# arduino-shield.net
KiCad netlist of a schematic drawn in EAGLE
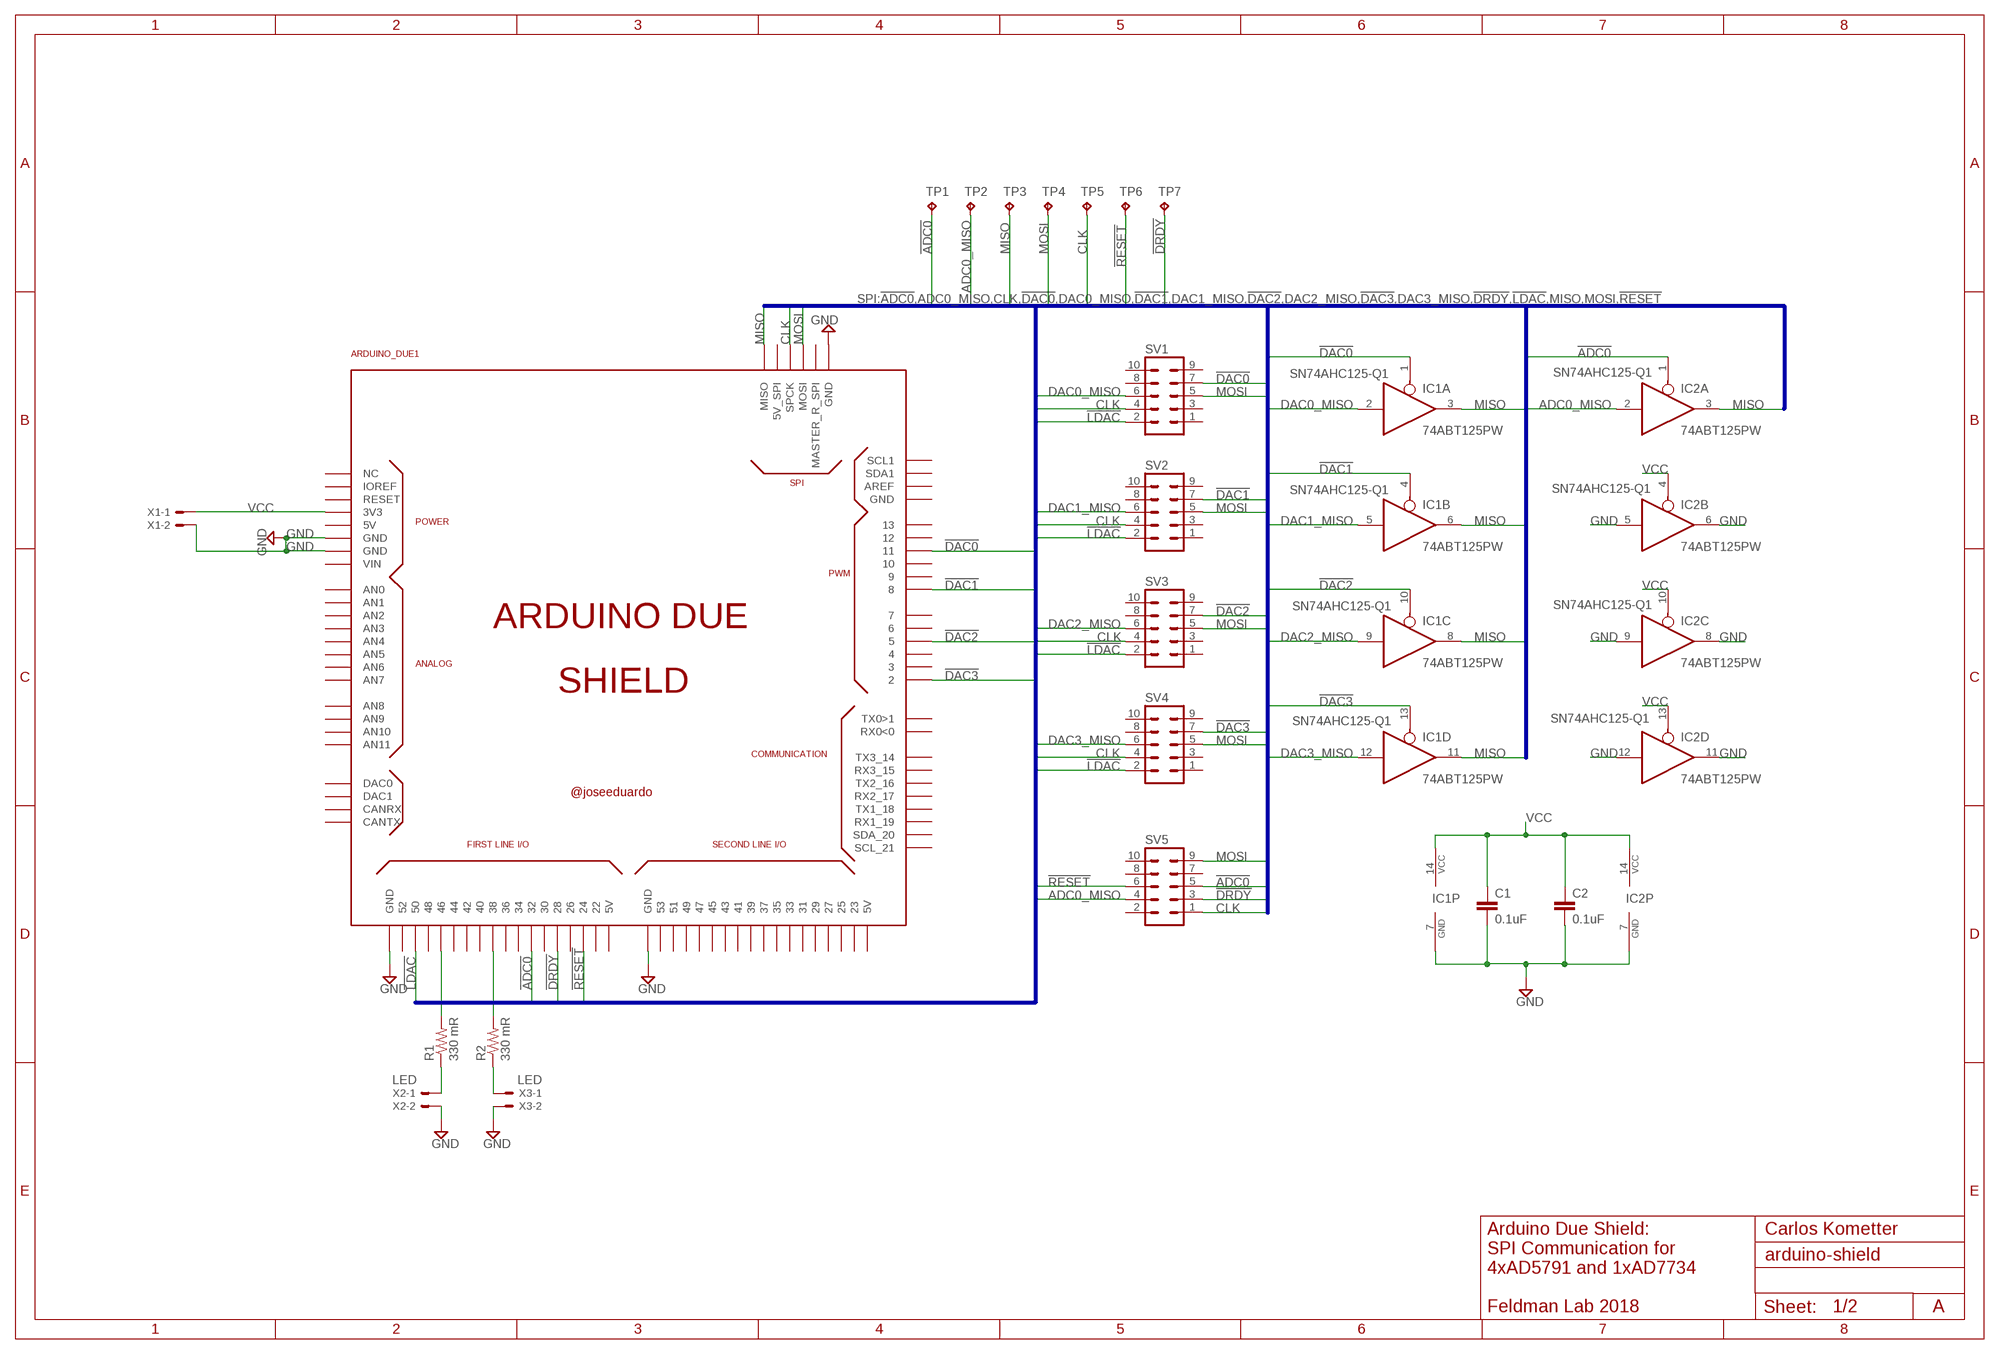
[diagram p0: schematic, sheet 1]
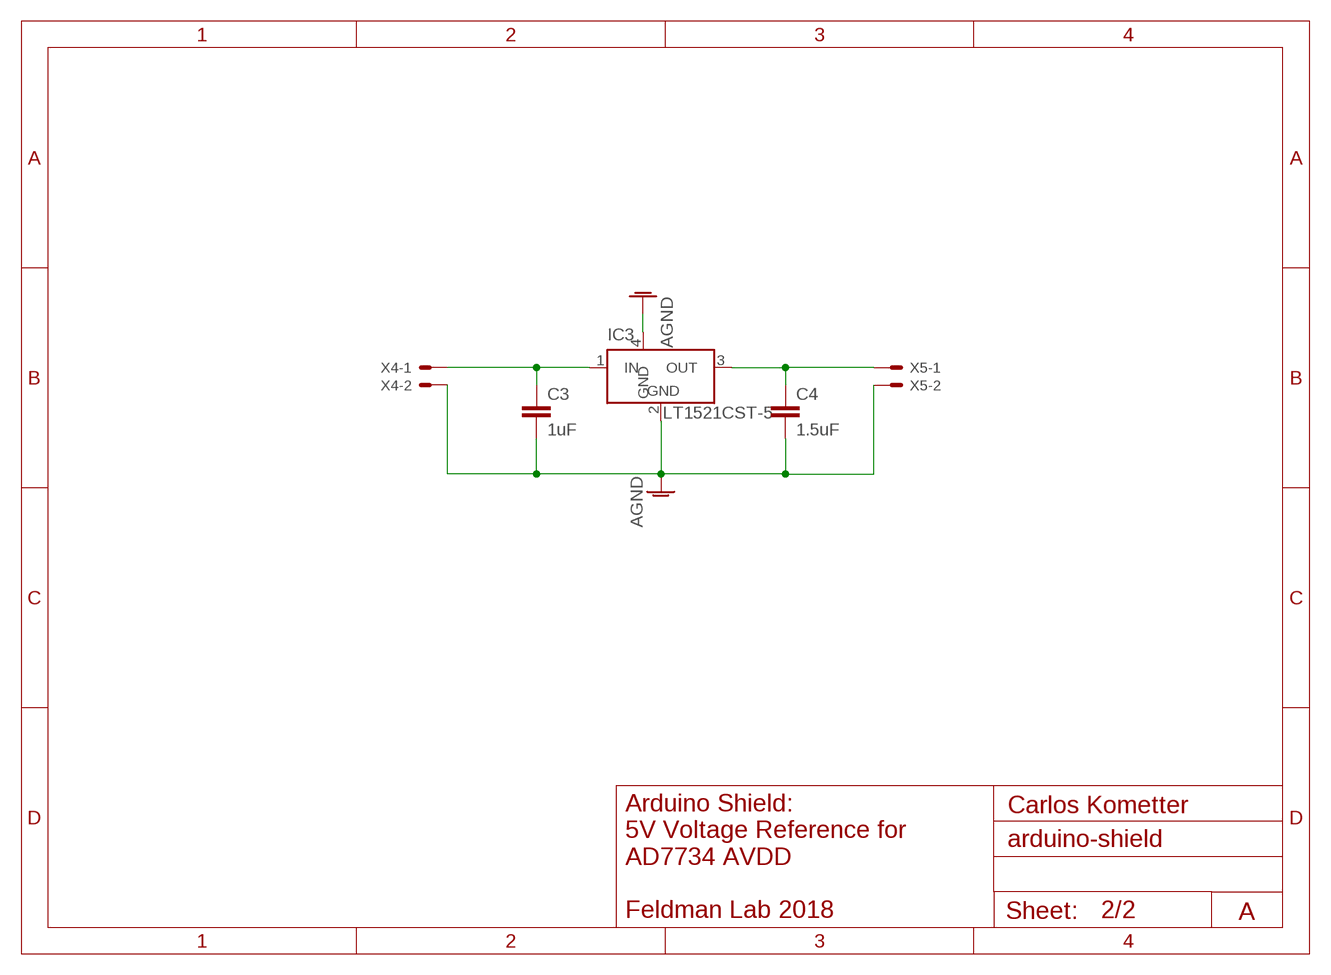
[diagram p1: schematic, sheet 2]

(export (version "E")
  (design (tool "Eeschema 10.0.6"))
  (components
    (comp (ref "C3")
      (value "1uF")
      (footprint "eagle-import:C0603")
      (libsource (lib "eagle-import") (part "C-EUC0603"))
    )
    (comp (ref "C4")
      (value "1.5uF")
      (footprint "eagle-import:C0603")
      (libsource (lib "eagle-import") (part "C-EUC0603"))
    )
    (comp (ref "IC3")
      (value "LT1129CST5")
      (footprint "eagle-import:SOT223")
      (fields (field (name "MPN") "LT1129CST-5#PBF"))
      (libsource (lib "eagle-import") (part "LT1129CST5"))
    )
    (comp (ref "X4")
      (value "22-23-2021")
      (footprint "eagle-import:22-23-2021")
      (fields (field (name "MF") "MOLEX"))
      (libsource (lib "eagle-import") (part "22-23-2021"))
    )
    (comp (ref "X5")
      (value "22-23-2021")
      (footprint "eagle-import:22-23-2021")
      (fields (field (name "MF") "MOLEX"))
      (libsource (lib "eagle-import") (part "22-23-2021"))
    )
    (comp (ref "ARDUINO_DUE1")
      (value "ARDUINO_DUE_SHIELD")
      (footprint "eagle-import:ARDUINO_DUE_SHIELD")
      (libsource (lib "eagle-import") (part "ARDUINO_DUE_SHIELD"))
    )
    (comp (ref "C1")
      (value "0.1uF")
      (footprint "eagle-import:C0603")
      (libsource (lib "eagle-import") (part "C-EUC0603"))
    )
    (comp (ref "C2")
      (value "0.1uF")
      (footprint "eagle-import:C0603")
      (libsource (lib "eagle-import") (part "C-EUC0603"))
    )
    (comp (ref "IC1")
      (value "74ABT125PW")
      (footprint "eagle-import:TSSOP14")
      (libsource (lib "eagle-import") (part "74125PWABT"))
    )
    (comp (ref "IC2")
      (value "74ABT125PW")
      (footprint "eagle-import:TSSOP14")
      (libsource (lib "eagle-import") (part "74125PWABT"))
    )
    (comp (ref "R1")
      (value "330 mR")
      (footprint "eagle-import:R1206")
      (libsource (lib "eagle-import") (part "R-US_R1206"))
    )
    (comp (ref "R2")
      (value "330 mR")
      (footprint "eagle-import:R1206")
      (libsource (lib "eagle-import") (part "R-US_R1206"))
    )
    (comp (ref "SV1")
      (value "MA05-2")
      (footprint "eagle-import:MA05-2")
      (libsource (lib "eagle-import") (part "MA05-2"))
    )
    (comp (ref "SV2")
      (value "MA05-2")
      (footprint "eagle-import:MA05-2")
      (libsource (lib "eagle-import") (part "MA05-2"))
    )
    (comp (ref "SV3")
      (value "MA05-2")
      (footprint "eagle-import:MA05-2")
      (libsource (lib "eagle-import") (part "MA05-2"))
    )
    (comp (ref "SV4")
      (value "MA05-2")
      (footprint "eagle-import:MA05-2")
      (libsource (lib "eagle-import") (part "MA05-2"))
    )
    (comp (ref "SV5")
      (value "MA05-2")
      (footprint "eagle-import:MA05-2")
      (libsource (lib "eagle-import") (part "MA05-2"))
    )
    (comp (ref "TP1")
      (value "TPPAD1-13")
      (footprint "eagle-import:P1-13")
      (libsource (lib "eagle-import") (part "TPPAD1-13"))
    )
    (comp (ref "TP2")
      (value "TPPAD1-13")
      (footprint "eagle-import:P1-13")
      (libsource (lib "eagle-import") (part "TPPAD1-13"))
    )
    (comp (ref "TP3")
      (value "TPPAD1-13")
      (footprint "eagle-import:P1-13")
      (libsource (lib "eagle-import") (part "TPPAD1-13"))
    )
    (comp (ref "TP4")
      (value "TPPAD1-13")
      (footprint "eagle-import:P1-13")
      (libsource (lib "eagle-import") (part "TPPAD1-13"))
    )
    (comp (ref "TP5")
      (value "TPPAD1-13")
      (footprint "eagle-import:P1-13")
      (libsource (lib "eagle-import") (part "TPPAD1-13"))
    )
    (comp (ref "TP6")
      (value "TPPAD1-13")
      (footprint "eagle-import:P1-13")
      (libsource (lib "eagle-import") (part "TPPAD1-13"))
    )
    (comp (ref "TP7")
      (value "TPPAD1-13")
      (footprint "eagle-import:P1-13")
      (libsource (lib "eagle-import") (part "TPPAD1-13"))
    )
    (comp (ref "X1")
      (value "22-23-2021")
      (footprint "eagle-import:22-23-2021")
      (fields (field (name "MF") "MOLEX"))
      (libsource (lib "eagle-import") (part "22-23-2021"))
    )
    (comp (ref "X2")
      (value "22-23-2021")
      (footprint "eagle-import:22-23-2021")
      (fields (field (name "MF") "MOLEX"))
      (libsource (lib "eagle-import") (part "22-23-2021"))
    )
    (comp (ref "X3")
      (value "22-23-2021")
      (footprint "eagle-import:22-23-2021")
      (fields (field (name "MF") "MOLEX"))
      (libsource (lib "eagle-import") (part "22-23-2021"))
    )
  )
  (nets
    (net (code "3") (name "ADC0_MISO") (class "Default")
      (node (ref "IC2") (pin "2") (pinfunction "I_2") (pintype "input"))
      (node (ref "SV5") (pin "4") (pinfunction "4_4") (pintype "passive"))
      (node (ref "TP2") (pin "TP") (pinfunction "TP_TP") (pintype "input"))
    )
    (net (code "4") (name "AGND") (class "Default")
      (node (ref "C3") (pin "2") (pinfunction "2_2") (pintype "passive"))
      (node (ref "C4") (pin "2") (pinfunction "2_2") (pintype "passive"))
      (node (ref "IC3") (pin "2") (pinfunction "GND_2") (pintype "power_in"))
      (node (ref "IC3") (pin "4") (pinfunction "GND_4") (pintype "power_in"))
      (node (ref "X4") (pin "2") (pinfunction "S_2") (pintype "passive"))
      (node (ref "X5") (pin "2") (pinfunction "S_2") (pintype "passive"))
    )
    (net (code "5") (name "CLK") (class "Default")
      (node (ref "ARDUINO_DUE1") (pin "SPCK") (pinfunction "SPCK_SPCK") (pintype "bidirectional"))
      (node (ref "SV1") (pin "4") (pinfunction "4_4") (pintype "passive"))
      (node (ref "SV2") (pin "4") (pinfunction "4_4") (pintype "passive"))
      (node (ref "SV3") (pin "4") (pinfunction "4_4") (pintype "passive"))
      (node (ref "SV4") (pin "4") (pinfunction "4_4") (pintype "passive"))
      (node (ref "SV5") (pin "1") (pinfunction "1_1") (pintype "passive"))
      (node (ref "TP5") (pin "TP") (pinfunction "TP_TP") (pintype "input"))
    )
    (net (code "6") (name "DAC0_MISO") (class "Default")
      (node (ref "IC1") (pin "2") (pinfunction "I_2") (pintype "input"))
      (node (ref "SV1") (pin "6") (pinfunction "6_6") (pintype "passive"))
    )
    (net (code "7") (name "DAC1_MISO") (class "Default")
      (node (ref "IC1") (pin "5") (pinfunction "I_5") (pintype "input"))
      (node (ref "SV2") (pin "6") (pinfunction "6_6") (pintype "passive"))
    )
    (net (code "8") (name "DAC2_MISO") (class "Default")
      (node (ref "IC1") (pin "9") (pinfunction "I_9") (pintype "input"))
      (node (ref "SV3") (pin "6") (pinfunction "6_6") (pintype "passive"))
    )
    (net (code "9") (name "DAC3_MISO") (class "Default")
      (node (ref "IC1") (pin "12") (pinfunction "I_12") (pintype "input"))
      (node (ref "SV4") (pin "6") (pinfunction "6_6") (pintype "passive"))
    )
    (net (code "10") (name "GND") (class "Default")
      (node (ref "ARDUINO_DUE1") (pin "GND") (pinfunction "GND_GND") (pintype "bidirectional"))
      (node (ref "ARDUINO_DUE1") (pin "GND_1") (pinfunction "GND_GND_1") (pintype "bidirectional"))
      (node (ref "ARDUINO_DUE1") (pin "GND_2") (pinfunction "GND_GND_2") (pintype "bidirectional"))
      (node (ref "ARDUINO_DUE1") (pin "GND_3") (pinfunction "GND_GND_3") (pintype "bidirectional"))
      (node (ref "ARDUINO_DUE1") (pin "GND_5") (pinfunction "GND_GND_5") (pintype "bidirectional"))
      (node (ref "C1") (pin "2") (pinfunction "2_2") (pintype "passive"))
      (node (ref "C2") (pin "2") (pinfunction "2_2") (pintype "passive"))
      (node (ref "IC1") (pin "7") (pinfunction "GND_7") (pintype "power_in"))
      (node (ref "IC2") (pin "11") (pinfunction "O_11") (pintype "tri_state"))
      (node (ref "IC2") (pin "12") (pinfunction "I_12") (pintype "input"))
      (node (ref "IC2") (pin "5") (pinfunction "I_5") (pintype "input"))
      (node (ref "IC2") (pin "6") (pinfunction "O_6") (pintype "tri_state"))
      (node (ref "IC2") (pin "7") (pinfunction "GND_7") (pintype "power_in"))
      (node (ref "IC2") (pin "8") (pinfunction "O_8") (pintype "tri_state"))
      (node (ref "IC2") (pin "9") (pinfunction "I_9") (pintype "input"))
      (node (ref "X1") (pin "2") (pinfunction "S_2") (pintype "passive"))
      (node (ref "X2") (pin "2") (pinfunction "S_2") (pintype "passive"))
      (node (ref "X3") (pin "2") (pinfunction "S_2") (pintype "passive"))
    )
    (net (code "11") (name "MISO") (class "Default")
      (node (ref "ARDUINO_DUE1") (pin "MISO") (pinfunction "MISO_MISO") (pintype "bidirectional"))
      (node (ref "IC1") (pin "11") (pinfunction "O_11") (pintype "tri_state"))
      (node (ref "IC1") (pin "3") (pinfunction "O_3") (pintype "tri_state"))
      (node (ref "IC1") (pin "6") (pinfunction "O_6") (pintype "tri_state"))
      (node (ref "IC1") (pin "8") (pinfunction "O_8") (pintype "tri_state"))
      (node (ref "IC2") (pin "3") (pinfunction "O_3") (pintype "tri_state"))
      (node (ref "TP3") (pin "TP") (pinfunction "TP_TP") (pintype "input"))
    )
    (net (code "12") (name "MOSI") (class "Default")
      (node (ref "ARDUINO_DUE1") (pin "MOSI") (pinfunction "MOSI_MOSI") (pintype "bidirectional"))
      (node (ref "SV1") (pin "5") (pinfunction "5_5") (pintype "passive"))
      (node (ref "SV2") (pin "5") (pinfunction "5_5") (pintype "passive"))
      (node (ref "SV3") (pin "5") (pinfunction "5_5") (pintype "passive"))
      (node (ref "SV4") (pin "5") (pinfunction "5_5") (pintype "passive"))
      (node (ref "SV5") (pin "9") (pinfunction "9_9") (pintype "passive"))
      (node (ref "TP4") (pin "TP") (pinfunction "TP_TP") (pintype "input"))
    )
    (net (code "13") (name "Net-(ARDUINO_DUE1-Pad38)") (class "Default")
      (node (ref "ARDUINO_DUE1") (pin "38") (pinfunction "38_38") (pintype "bidirectional"))
      (node (ref "R2") (pin "2") (pinfunction "2_2") (pintype "passive"))
    )
    (net (code "14") (name "Net-(ARDUINO_DUE1-Pad46)") (class "Default")
      (node (ref "ARDUINO_DUE1") (pin "46") (pinfunction "46_46") (pintype "bidirectional"))
      (node (ref "R1") (pin "2") (pinfunction "2_2") (pintype "passive"))
    )
    (net (code "15") (name "Net-(IC3A-IN)") (class "Default")
      (node (ref "C3") (pin "1") (pinfunction "1_1") (pintype "passive"))
      (node (ref "IC3") (pin "1") (pinfunction "IN_1") (pintype "input"))
      (node (ref "X4") (pin "1") (pinfunction "S_1") (pintype "passive"))
    )
    (net (code "16") (name "Net-(IC3A-OUT)") (class "Default")
      (node (ref "C4") (pin "1") (pinfunction "1_1") (pintype "passive"))
      (node (ref "IC3") (pin "3") (pinfunction "OUT_3") (pintype "output"))
      (node (ref "X5") (pin "1") (pinfunction "S_1") (pintype "passive"))
    )
    (net (code "17") (name "Net-(X2A-S)") (class "Default")
      (node (ref "R1") (pin "1") (pinfunction "1_1") (pintype "passive"))
      (node (ref "X2") (pin "1") (pinfunction "S_1") (pintype "passive"))
    )
    (net (code "18") (name "Net-(X3A-S)") (class "Default")
      (node (ref "R2") (pin "1") (pinfunction "1_1") (pintype "passive"))
      (node (ref "X3") (pin "1") (pinfunction "S_1") (pintype "passive"))
    )
    (net (code "19") (name "VCC") (class "Default")
      (node (ref "ARDUINO_DUE1") (pin "3V3") (pinfunction "3V3_3V3") (pintype "bidirectional"))
      (node (ref "C1") (pin "1") (pinfunction "1_1") (pintype "passive"))
      (node (ref "C2") (pin "1") (pinfunction "1_1") (pintype "passive"))
      (node (ref "IC1") (pin "14") (pinfunction "VCC_14") (pintype "power_in"))
      (node (ref "IC2") (pin "10") (pinfunction "OE_10") (pintype "input"))
      (node (ref "IC2") (pin "13") (pinfunction "OE_13") (pintype "input"))
      (node (ref "IC2") (pin "14") (pinfunction "VCC_14") (pintype "power_in"))
      (node (ref "IC2") (pin "4") (pinfunction "OE_4") (pintype "input"))
      (node (ref "X1") (pin "1") (pinfunction "S_1") (pintype "passive"))
    )
    (net (code "20") (name "unconnected-(ARDUINO_DUE1-5V-Pad5V0)") (class "Default")
      (node (ref "ARDUINO_DUE1") (pin "5V0") (pinfunction "5V_5V0") (pintype "bidirectional"))
    )
    (net (code "21") (name "unconnected-(ARDUINO_DUE1-5V-Pad5V0_1)") (class "Default")
      (node (ref "ARDUINO_DUE1") (pin "5V0_1") (pinfunction "5V_5V0_1") (pintype "bidirectional"))
    )
    (net (code "22") (name "unconnected-(ARDUINO_DUE1-5V-Pad5V0_2)") (class "Default")
      (node (ref "ARDUINO_DUE1") (pin "5V0_2") (pinfunction "5V_5V0_2") (pintype "bidirectional"))
    )
    (net (code "23") (name "unconnected-(ARDUINO_DUE1-5V_SPI-Pad5V_2)") (class "Default")
      (node (ref "ARDUINO_DUE1") (pin "5V_2") (pinfunction "5V_SPI_5V_2") (pintype "bidirectional"))
    )
    (net (code "24") (name "unconnected-(ARDUINO_DUE1-AN0-PadA0)") (class "Default")
      (node (ref "ARDUINO_DUE1") (pin "A0") (pinfunction "AN0_A0") (pintype "bidirectional"))
    )
    (net (code "25") (name "unconnected-(ARDUINO_DUE1-AN1-PadA1)") (class "Default")
      (node (ref "ARDUINO_DUE1") (pin "A1") (pinfunction "AN1_A1") (pintype "bidirectional"))
    )
    (net (code "26") (name "unconnected-(ARDUINO_DUE1-AN2-PadA2)") (class "Default")
      (node (ref "ARDUINO_DUE1") (pin "A2") (pinfunction "AN2_A2") (pintype "bidirectional"))
    )
    (net (code "27") (name "unconnected-(ARDUINO_DUE1-AN3-PadA3)") (class "Default")
      (node (ref "ARDUINO_DUE1") (pin "A3") (pinfunction "AN3_A3") (pintype "bidirectional"))
    )
    (net (code "28") (name "unconnected-(ARDUINO_DUE1-AN4-PadA4)") (class "Default")
      (node (ref "ARDUINO_DUE1") (pin "A4") (pinfunction "AN4_A4") (pintype "bidirectional"))
    )
    (net (code "29") (name "unconnected-(ARDUINO_DUE1-AN5-PadA5)") (class "Default")
      (node (ref "ARDUINO_DUE1") (pin "A5") (pinfunction "AN5_A5") (pintype "bidirectional"))
    )
    (net (code "30") (name "unconnected-(ARDUINO_DUE1-AN6-PadA6)") (class "Default")
      (node (ref "ARDUINO_DUE1") (pin "A6") (pinfunction "AN6_A6") (pintype "bidirectional"))
    )
    (net (code "31") (name "unconnected-(ARDUINO_DUE1-AN7-PadA7)") (class "Default")
      (node (ref "ARDUINO_DUE1") (pin "A7") (pinfunction "AN7_A7") (pintype "bidirectional"))
    )
    (net (code "32") (name "unconnected-(ARDUINO_DUE1-AN8-PadA8)") (class "Default")
      (node (ref "ARDUINO_DUE1") (pin "A8") (pinfunction "AN8_A8") (pintype "bidirectional"))
    )
    (net (code "33") (name "unconnected-(ARDUINO_DUE1-AN9-PadA9)") (class "Default")
      (node (ref "ARDUINO_DUE1") (pin "A9") (pinfunction "AN9_A9") (pintype "bidirectional"))
    )
    (net (code "34") (name "unconnected-(ARDUINO_DUE1-AN10-PadA10)") (class "Default")
      (node (ref "ARDUINO_DUE1") (pin "A10") (pinfunction "AN10_A10") (pintype "bidirectional"))
    )
    (net (code "35") (name "unconnected-(ARDUINO_DUE1-AN11-PadA11)") (class "Default")
      (node (ref "ARDUINO_DUE1") (pin "A11") (pinfunction "AN11_A11") (pintype "bidirectional"))
    )
    (net (code "36") (name "unconnected-(ARDUINO_DUE1-GND-PadGND_4)") (class "Default")
      (node (ref "ARDUINO_DUE1") (pin "GND_4") (pinfunction "GND_GND_4") (pintype "bidirectional"))
    )
    (net (code "37") (name "unconnected-(ARDUINO_DUE1-MASTER_R_SPI-PadMASTER_RESET_SPI)") (class "Default")
      (node (ref "ARDUINO_DUE1") (pin "MASTER_RESET_SPI") (pinfunction "MASTER_R_SPI_MASTER_RESET_SPI") (pintype "bidirectional"))
    )
    (net (code "38") (name "unconnected-(ARDUINO_DUE1-NC-PadNC_2)") (class "Default")
      (node (ref "ARDUINO_DUE1") (pin "NC_2") (pinfunction "NC_NC_2") (pintype "no_connect"))
    )
    (net (code "39") (name "unconnected-(ARDUINO_DUE1-Pad3)") (class "Default")
      (node (ref "ARDUINO_DUE1") (pin "3") (pinfunction "3_3") (pintype "bidirectional"))
    )
    (net (code "40") (name "unconnected-(ARDUINO_DUE1-Pad4)") (class "Default")
      (node (ref "ARDUINO_DUE1") (pin "4") (pinfunction "4_4") (pintype "bidirectional"))
    )
    (net (code "41") (name "unconnected-(ARDUINO_DUE1-Pad6)") (class "Default")
      (node (ref "ARDUINO_DUE1") (pin "6") (pinfunction "6_6") (pintype "bidirectional"))
    )
    (net (code "42") (name "unconnected-(ARDUINO_DUE1-Pad7)") (class "Default")
      (node (ref "ARDUINO_DUE1") (pin "7") (pinfunction "7_7") (pintype "bidirectional"))
    )
    (net (code "43") (name "unconnected-(ARDUINO_DUE1-Pad9)") (class "Default")
      (node (ref "ARDUINO_DUE1") (pin "9") (pinfunction "9_9") (pintype "bidirectional"))
    )
    (net (code "44") (name "unconnected-(ARDUINO_DUE1-Pad10)") (class "Default")
      (node (ref "ARDUINO_DUE1") (pin "10") (pinfunction "10_10") (pintype "bidirectional"))
    )
    (net (code "45") (name "unconnected-(ARDUINO_DUE1-Pad12)") (class "Default")
      (node (ref "ARDUINO_DUE1") (pin "12") (pinfunction "12_12") (pintype "bidirectional"))
    )
    (net (code "46") (name "unconnected-(ARDUINO_DUE1-Pad13)") (class "Default")
      (node (ref "ARDUINO_DUE1") (pin "13") (pinfunction "13_13") (pintype "bidirectional"))
    )
    (net (code "47") (name "unconnected-(ARDUINO_DUE1-Pad22)") (class "Default")
      (node (ref "ARDUINO_DUE1") (pin "22") (pinfunction "22_22") (pintype "bidirectional"))
    )
    (net (code "48") (name "unconnected-(ARDUINO_DUE1-Pad23)") (class "Default")
      (node (ref "ARDUINO_DUE1") (pin "23") (pinfunction "23_23") (pintype "bidirectional"))
    )
    (net (code "49") (name "unconnected-(ARDUINO_DUE1-Pad25)") (class "Default")
      (node (ref "ARDUINO_DUE1") (pin "25") (pinfunction "25_25") (pintype "bidirectional"))
    )
    (net (code "50") (name "unconnected-(ARDUINO_DUE1-Pad26)") (class "Default")
      (node (ref "ARDUINO_DUE1") (pin "26") (pinfunction "26_26") (pintype "bidirectional"))
    )
    (net (code "51") (name "unconnected-(ARDUINO_DUE1-Pad27)") (class "Default")
      (node (ref "ARDUINO_DUE1") (pin "27") (pinfunction "27_27") (pintype "bidirectional"))
    )
    (net (code "52") (name "unconnected-(ARDUINO_DUE1-Pad29)") (class "Default")
      (node (ref "ARDUINO_DUE1") (pin "29") (pinfunction "29_29") (pintype "bidirectional"))
    )
    (net (code "53") (name "unconnected-(ARDUINO_DUE1-Pad30)") (class "Default")
      (node (ref "ARDUINO_DUE1") (pin "30") (pinfunction "30_30") (pintype "bidirectional"))
    )
    (net (code "54") (name "unconnected-(ARDUINO_DUE1-Pad31)") (class "Default")
      (node (ref "ARDUINO_DUE1") (pin "31") (pinfunction "31_31") (pintype "bidirectional"))
    )
    (net (code "55") (name "unconnected-(ARDUINO_DUE1-Pad33)") (class "Default")
      (node (ref "ARDUINO_DUE1") (pin "33") (pinfunction "33_33") (pintype "bidirectional"))
    )
    (net (code "56") (name "unconnected-(ARDUINO_DUE1-Pad34)") (class "Default")
      (node (ref "ARDUINO_DUE1") (pin "34") (pinfunction "34_34") (pintype "bidirectional"))
    )
    (net (code "57") (name "unconnected-(ARDUINO_DUE1-Pad35)") (class "Default")
      (node (ref "ARDUINO_DUE1") (pin "35") (pinfunction "35_35") (pintype "bidirectional"))
    )
    (net (code "58") (name "unconnected-(ARDUINO_DUE1-Pad36)") (class "Default")
      (node (ref "ARDUINO_DUE1") (pin "36") (pinfunction "36_36") (pintype "bidirectional"))
    )
    (net (code "59") (name "unconnected-(ARDUINO_DUE1-Pad37)") (class "Default")
      (node (ref "ARDUINO_DUE1") (pin "37") (pinfunction "37_37") (pintype "bidirectional"))
    )
    (net (code "60") (name "unconnected-(ARDUINO_DUE1-Pad39)") (class "Default")
      (node (ref "ARDUINO_DUE1") (pin "39") (pinfunction "39_39") (pintype "bidirectional"))
    )
    (net (code "61") (name "unconnected-(ARDUINO_DUE1-Pad40)") (class "Default")
      (node (ref "ARDUINO_DUE1") (pin "40") (pinfunction "40_40") (pintype "bidirectional"))
    )
    (net (code "62") (name "unconnected-(ARDUINO_DUE1-Pad41)") (class "Default")
      (node (ref "ARDUINO_DUE1") (pin "41") (pinfunction "41_41") (pintype "bidirectional"))
    )
    (net (code "63") (name "unconnected-(ARDUINO_DUE1-Pad42)") (class "Default")
      (node (ref "ARDUINO_DUE1") (pin "42") (pinfunction "42_42") (pintype "bidirectional"))
    )
    (net (code "64") (name "unconnected-(ARDUINO_DUE1-Pad43)") (class "Default")
      (node (ref "ARDUINO_DUE1") (pin "43") (pinfunction "43_43") (pintype "bidirectional"))
    )
    (net (code "65") (name "unconnected-(ARDUINO_DUE1-Pad44)") (class "Default")
      (node (ref "ARDUINO_DUE1") (pin "44") (pinfunction "44_44") (pintype "bidirectional"))
    )
    (net (code "66") (name "unconnected-(ARDUINO_DUE1-Pad45)") (class "Default")
      (node (ref "ARDUINO_DUE1") (pin "45") (pinfunction "45_45") (pintype "bidirectional"))
    )
    (net (code "67") (name "unconnected-(ARDUINO_DUE1-Pad47)") (class "Default")
      (node (ref "ARDUINO_DUE1") (pin "47") (pinfunction "47_47") (pintype "bidirectional"))
    )
    (net (code "68") (name "unconnected-(ARDUINO_DUE1-Pad48)") (class "Default")
      (node (ref "ARDUINO_DUE1") (pin "48") (pinfunction "48_48") (pintype "bidirectional"))
    )
    (net (code "69") (name "unconnected-(ARDUINO_DUE1-Pad49)") (class "Default")
      (node (ref "ARDUINO_DUE1") (pin "49") (pinfunction "49_49") (pintype "bidirectional"))
    )
    (net (code "70") (name "unconnected-(ARDUINO_DUE1-Pad51)") (class "Default")
      (node (ref "ARDUINO_DUE1") (pin "51") (pinfunction "51_51") (pintype "bidirectional"))
    )
    (net (code "71") (name "unconnected-(ARDUINO_DUE1-Pad52)") (class "Default")
      (node (ref "ARDUINO_DUE1") (pin "52") (pinfunction "52_52") (pintype "bidirectional"))
    )
    (net (code "72") (name "unconnected-(ARDUINO_DUE1-Pad53)") (class "Default")
      (node (ref "ARDUINO_DUE1") (pin "53") (pinfunction "53_53") (pintype "bidirectional"))
    )
    (net (code "73") (name "unconnected-(ARDUINO_DUE1-PadAREF)") (class "Default")
      (node (ref "ARDUINO_DUE1") (pin "AREF") (pinfunction "AREF_AREF") (pintype "bidirectional"))
    )
    (net (code "74") (name "unconnected-(ARDUINO_DUE1-PadCANRX)") (class "Default")
      (node (ref "ARDUINO_DUE1") (pin "CANRX") (pinfunction "CANRX_CANRX") (pintype "bidirectional"))
    )
    (net (code "75") (name "unconnected-(ARDUINO_DUE1-PadCANTX)") (class "Default")
      (node (ref "ARDUINO_DUE1") (pin "CANTX") (pinfunction "CANTX_CANTX") (pintype "bidirectional"))
    )
    (net (code "76") (name "unconnected-(ARDUINO_DUE1-PadDAC0)") (class "Default")
      (node (ref "ARDUINO_DUE1") (pin "DAC0") (pinfunction "DAC0_DAC0") (pintype "bidirectional"))
    )
    (net (code "77") (name "unconnected-(ARDUINO_DUE1-PadDAC1)") (class "Default")
      (node (ref "ARDUINO_DUE1") (pin "DAC1") (pinfunction "DAC1_DAC1") (pintype "bidirectional"))
    )
    (net (code "78") (name "unconnected-(ARDUINO_DUE1-PadIOREF)") (class "Default")
      (node (ref "ARDUINO_DUE1") (pin "IOREF") (pinfunction "IOREF_IOREF") (pintype "bidirectional"))
    )
    (net (code "79") (name "unconnected-(ARDUINO_DUE1-PadRESET)") (class "Default")
      (node (ref "ARDUINO_DUE1") (pin "RESET") (pinfunction "RESET_RESET") (pintype "bidirectional"))
    )
    (net (code "80") (name "unconnected-(ARDUINO_DUE1-PadSCL1)") (class "Default")
      (node (ref "ARDUINO_DUE1") (pin "SCL1") (pinfunction "SCL1_SCL1") (pintype "bidirectional"))
    )
    (net (code "81") (name "unconnected-(ARDUINO_DUE1-PadSDA1)") (class "Default")
      (node (ref "ARDUINO_DUE1") (pin "SDA1") (pinfunction "SDA1_SDA1") (pintype "bidirectional"))
    )
    (net (code "82") (name "unconnected-(ARDUINO_DUE1-PadVIN)") (class "Default")
      (node (ref "ARDUINO_DUE1") (pin "VIN") (pinfunction "VIN_VIN") (pintype "bidirectional"))
    )
    (net (code "83") (name "unconnected-(ARDUINO_DUE1-RX0<0-Pad0)") (class "Default")
      (node (ref "ARDUINO_DUE1") (pin "0") (pinfunction "RX0<0_0") (pintype "bidirectional"))
    )
    (net (code "84") (name "unconnected-(ARDUINO_DUE1-RX1_19-Pad19)") (class "Default")
      (node (ref "ARDUINO_DUE1") (pin "19") (pinfunction "RX1_19_19") (pintype "bidirectional"))
    )
    (net (code "85") (name "unconnected-(ARDUINO_DUE1-RX2_17-Pad17)") (class "Default")
      (node (ref "ARDUINO_DUE1") (pin "17") (pinfunction "RX2_17_17") (pintype "bidirectional"))
    )
    (net (code "86") (name "unconnected-(ARDUINO_DUE1-RX3_15-Pad15)") (class "Default")
      (node (ref "ARDUINO_DUE1") (pin "15") (pinfunction "RX3_15_15") (pintype "bidirectional"))
    )
    (net (code "87") (name "unconnected-(ARDUINO_DUE1-SCL_21-Pad21)") (class "Default")
      (node (ref "ARDUINO_DUE1") (pin "21") (pinfunction "SCL_21_21") (pintype "bidirectional"))
    )
    (net (code "88") (name "unconnected-(ARDUINO_DUE1-SDA_20-Pad20)") (class "Default")
      (node (ref "ARDUINO_DUE1") (pin "20") (pinfunction "SDA_20_20") (pintype "bidirectional"))
    )
    (net (code "89") (name "unconnected-(ARDUINO_DUE1-TX0>1-Pad1)") (class "Default")
      (node (ref "ARDUINO_DUE1") (pin "1") (pinfunction "TX0>1_1") (pintype "bidirectional"))
    )
    (net (code "90") (name "unconnected-(ARDUINO_DUE1-TX1_18-Pad18)") (class "Default")
      (node (ref "ARDUINO_DUE1") (pin "18") (pinfunction "TX1_18_18") (pintype "bidirectional"))
    )
    (net (code "91") (name "unconnected-(ARDUINO_DUE1-TX2_16-Pad16)") (class "Default")
      (node (ref "ARDUINO_DUE1") (pin "16") (pinfunction "TX2_16_16") (pintype "bidirectional"))
    )
    (net (code "92") (name "unconnected-(ARDUINO_DUE1-TX3_14-Pad14)") (class "Default")
      (node (ref "ARDUINO_DUE1") (pin "14") (pinfunction "TX3_14_14") (pintype "bidirectional"))
    )
    (net (code "93") (name "unconnected-(SV1-Pad1)") (class "Default")
      (node (ref "SV1") (pin "1") (pinfunction "1_1") (pintype "passive"))
    )
    (net (code "94") (name "unconnected-(SV1-Pad3)") (class "Default")
      (node (ref "SV1") (pin "3") (pinfunction "3_3") (pintype "passive"))
    )
    (net (code "95") (name "unconnected-(SV1-Pad8)") (class "Default")
      (node (ref "SV1") (pin "8") (pinfunction "8_8") (pintype "passive"))
    )
    (net (code "96") (name "unconnected-(SV1-Pad9)") (class "Default")
      (node (ref "SV1") (pin "9") (pinfunction "9_9") (pintype "passive"))
    )
    (net (code "97") (name "unconnected-(SV1-Pad10)") (class "Default")
      (node (ref "SV1") (pin "10") (pinfunction "10_10") (pintype "passive"))
    )
    (net (code "98") (name "unconnected-(SV2-Pad1)") (class "Default")
      (node (ref "SV2") (pin "1") (pinfunction "1_1") (pintype "passive"))
    )
    (net (code "99") (name "unconnected-(SV2-Pad3)") (class "Default")
      (node (ref "SV2") (pin "3") (pinfunction "3_3") (pintype "passive"))
    )
    (net (code "100") (name "unconnected-(SV2-Pad8)") (class "Default")
      (node (ref "SV2") (pin "8") (pinfunction "8_8") (pintype "passive"))
    )
    (net (code "101") (name "unconnected-(SV2-Pad9)") (class "Default")
      (node (ref "SV2") (pin "9") (pinfunction "9_9") (pintype "passive"))
    )
    (net (code "102") (name "unconnected-(SV2-Pad10)") (class "Default")
      (node (ref "SV2") (pin "10") (pinfunction "10_10") (pintype "passive"))
    )
    (net (code "103") (name "unconnected-(SV3-Pad1)") (class "Default")
      (node (ref "SV3") (pin "1") (pinfunction "1_1") (pintype "passive"))
    )
    (net (code "104") (name "unconnected-(SV3-Pad3)") (class "Default")
      (node (ref "SV3") (pin "3") (pinfunction "3_3") (pintype "passive"))
    )
    (net (code "105") (name "unconnected-(SV3-Pad8)") (class "Default")
      (node (ref "SV3") (pin "8") (pinfunction "8_8") (pintype "passive"))
    )
    (net (code "106") (name "unconnected-(SV3-Pad9)") (class "Default")
      (node (ref "SV3") (pin "9") (pinfunction "9_9") (pintype "passive"))
    )
    (net (code "107") (name "unconnected-(SV3-Pad10)") (class "Default")
      (node (ref "SV3") (pin "10") (pinfunction "10_10") (pintype "passive"))
    )
    (net (code "108") (name "unconnected-(SV4-Pad1)") (class "Default")
      (node (ref "SV4") (pin "1") (pinfunction "1_1") (pintype "passive"))
    )
    (net (code "109") (name "unconnected-(SV4-Pad3)") (class "Default")
      (node (ref "SV4") (pin "3") (pinfunction "3_3") (pintype "passive"))
    )
    (net (code "110") (name "unconnected-(SV4-Pad8)") (class "Default")
      (node (ref "SV4") (pin "8") (pinfunction "8_8") (pintype "passive"))
    )
    (net (code "111") (name "unconnected-(SV4-Pad9)") (class "Default")
      (node (ref "SV4") (pin "9") (pinfunction "9_9") (pintype "passive"))
    )
    (net (code "112") (name "unconnected-(SV4-Pad10)") (class "Default")
      (node (ref "SV4") (pin "10") (pinfunction "10_10") (pintype "passive"))
    )
    (net (code "113") (name "unconnected-(SV5-Pad2)") (class "Default")
      (node (ref "SV5") (pin "2") (pinfunction "2_2") (pintype "passive"))
    )
    (net (code "114") (name "unconnected-(SV5-Pad7)") (class "Default")
      (node (ref "SV5") (pin "7") (pinfunction "7_7") (pintype "passive"))
    )
    (net (code "115") (name "unconnected-(SV5-Pad8)") (class "Default")
      (node (ref "SV5") (pin "8") (pinfunction "8_8") (pintype "passive"))
    )
    (net (code "116") (name "unconnected-(SV5-Pad10)") (class "Default")
      (node (ref "SV5") (pin "10") (pinfunction "10_10") (pintype "passive"))
    )
    (net (code "117") (name "~{ADC0}") (class "Default")
      (node (ref "ARDUINO_DUE1") (pin "32") (pinfunction "32_32") (pintype "bidirectional"))
      (node (ref "IC2") (pin "1") (pinfunction "OE_1") (pintype "input"))
      (node (ref "SV5") (pin "5") (pinfunction "5_5") (pintype "passive"))
      (node (ref "TP1") (pin "TP") (pinfunction "TP_TP") (pintype "input"))
    )
    (net (code "118") (name "~{DAC0}") (class "Default")
      (node (ref "ARDUINO_DUE1") (pin "11") (pinfunction "11_11") (pintype "bidirectional"))
      (node (ref "IC1") (pin "1") (pinfunction "OE_1") (pintype "input"))
      (node (ref "SV1") (pin "7") (pinfunction "7_7") (pintype "passive"))
    )
    (net (code "119") (name "~{DAC1}") (class "Default")
      (node (ref "ARDUINO_DUE1") (pin "8") (pinfunction "8_8") (pintype "bidirectional"))
      (node (ref "IC1") (pin "4") (pinfunction "OE_4") (pintype "input"))
      (node (ref "SV2") (pin "7") (pinfunction "7_7") (pintype "passive"))
    )
    (net (code "120") (name "~{DAC2}") (class "Default")
      (node (ref "ARDUINO_DUE1") (pin "5") (pinfunction "5_5") (pintype "bidirectional"))
      (node (ref "IC1") (pin "10") (pinfunction "OE_10") (pintype "input"))
      (node (ref "SV3") (pin "7") (pinfunction "7_7") (pintype "passive"))
    )
    (net (code "121") (name "~{DAC3}") (class "Default")
      (node (ref "ARDUINO_DUE1") (pin "2") (pinfunction "2_2") (pintype "bidirectional"))
      (node (ref "IC1") (pin "13") (pinfunction "OE_13") (pintype "input"))
      (node (ref "SV4") (pin "7") (pinfunction "7_7") (pintype "passive"))
    )
    (net (code "122") (name "~{DRDY}") (class "Default")
      (node (ref "ARDUINO_DUE1") (pin "28") (pinfunction "28_28") (pintype "bidirectional"))
      (node (ref "SV5") (pin "3") (pinfunction "3_3") (pintype "passive"))
      (node (ref "TP7") (pin "TP") (pinfunction "TP_TP") (pintype "input"))
    )
    (net (code "123") (name "~{LDAC}") (class "Default")
      (node (ref "ARDUINO_DUE1") (pin "50") (pinfunction "50_50") (pintype "bidirectional"))
      (node (ref "SV1") (pin "2") (pinfunction "2_2") (pintype "passive"))
      (node (ref "SV2") (pin "2") (pinfunction "2_2") (pintype "passive"))
      (node (ref "SV3") (pin "2") (pinfunction "2_2") (pintype "passive"))
      (node (ref "SV4") (pin "2") (pinfunction "2_2") (pintype "passive"))
    )
    (net (code "124") (name "~{RESET}") (class "Default")
      (node (ref "ARDUINO_DUE1") (pin "24") (pinfunction "24_24") (pintype "bidirectional"))
      (node (ref "SV5") (pin "6") (pinfunction "6_6") (pintype "passive"))
      (node (ref "TP6") (pin "TP") (pinfunction "TP_TP") (pintype "input"))
    )
  )
)
